# kr1_3.net
KiCad netlist of a schematic drawn in Altium Designer
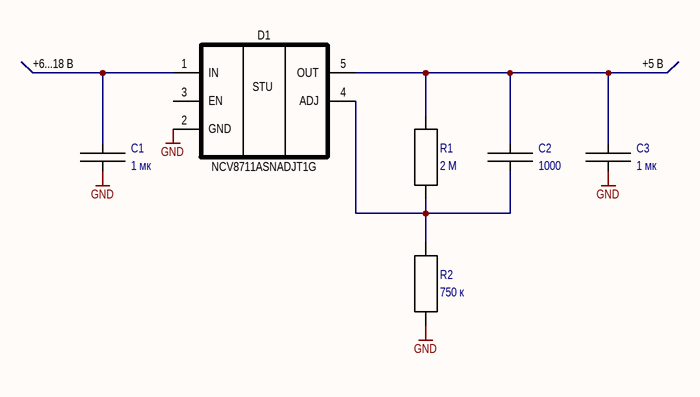
[diagram p0: kr1_3.SchDoc]

(export (version "E")
  (design (tool "Eeschema 10.0.6"))
  (components
    (comp (ref "C1")
      (value "1 мк")
      (fields (field (name "Comment") "1 мкФ ±* * * *, *"))
      (libsource (lib "STO") (part "C"))
    )
    (comp (ref "C2")
      (value "1000")
      (fields (field (name "Comment") "1000Ф ±* * * *, *"))
      (libsource (lib "STO") (part "C"))
    )
    (comp (ref "C3")
      (value "1 мк")
      (fields (field (name "Comment") "1 мкФ ±* * * *, *"))
      (libsource (lib "STO") (part "C"))
    )
    (comp (ref "D1") (value "NCV8711ASNADJT1G") (libsource (lib "STO") (part "NCV8711")))
    (comp (ref "R1")
      (value "2 М")
      (fields (field (name "Comment") "2 МОм ±* *, *"))
      (libsource (lib "STO") (part "R"))
    )
    (comp (ref "R2")
      (value "750 к")
      (fields (field (name "Comment") "750 кОм ±* *, *"))
      (libsource (lib "STO") (part "R"))
    )
  )
  (nets
    (net (code "1") (name "GND") (class "Default")
      (node (ref "C1") (pin "1") (pinfunction "1_1") (pintype "passive"))
      (node (ref "C3") (pin "1") (pinfunction "1_1") (pintype "passive"))
      (node (ref "D1") (pin "2") (pinfunction "GND_2") (pintype "passive"))
      (node (ref "R2") (pin "2") (pinfunction "2_2") (pintype "passive"))
    )
    (net (code "2") (name "Net-(D1-ADJ)") (class "Default")
      (node (ref "C2") (pin "1") (pinfunction "1_1") (pintype "passive"))
      (node (ref "D1") (pin "4") (pinfunction "ADJ_4") (pintype "passive"))
      (node (ref "R1") (pin "2") (pinfunction "2_2") (pintype "passive"))
      (node (ref "R2") (pin "1") (pinfunction "1_1") (pintype "passive"))
    )
    (net (code "3") (name "Net-(D1-IN)") (class "Default")
      (node (ref "C1") (pin "2") (pinfunction "2_2") (pintype "passive"))
      (node (ref "D1") (pin "1") (pinfunction "IN_1") (pintype "passive"))
    )
    (net (code "4") (name "Net-(D1-OUT)") (class "Default")
      (node (ref "C2") (pin "2") (pinfunction "2_2") (pintype "passive"))
      (node (ref "C3") (pin "2") (pinfunction "2_2") (pintype "passive"))
      (node (ref "D1") (pin "5") (pinfunction "OUT_5") (pintype "passive"))
      (node (ref "R1") (pin "1") (pinfunction "1_1") (pintype "passive"))
    )
    (net (code "5") (name "unconnected-(D1-EN-Pad3)") (class "Default")
      (node (ref "D1") (pin "3") (pinfunction "EN_3") (pintype "passive"))
    )
  )
)
